# 60_keyboard.net
KiCad netlist of a schematic drawn in EAGLE
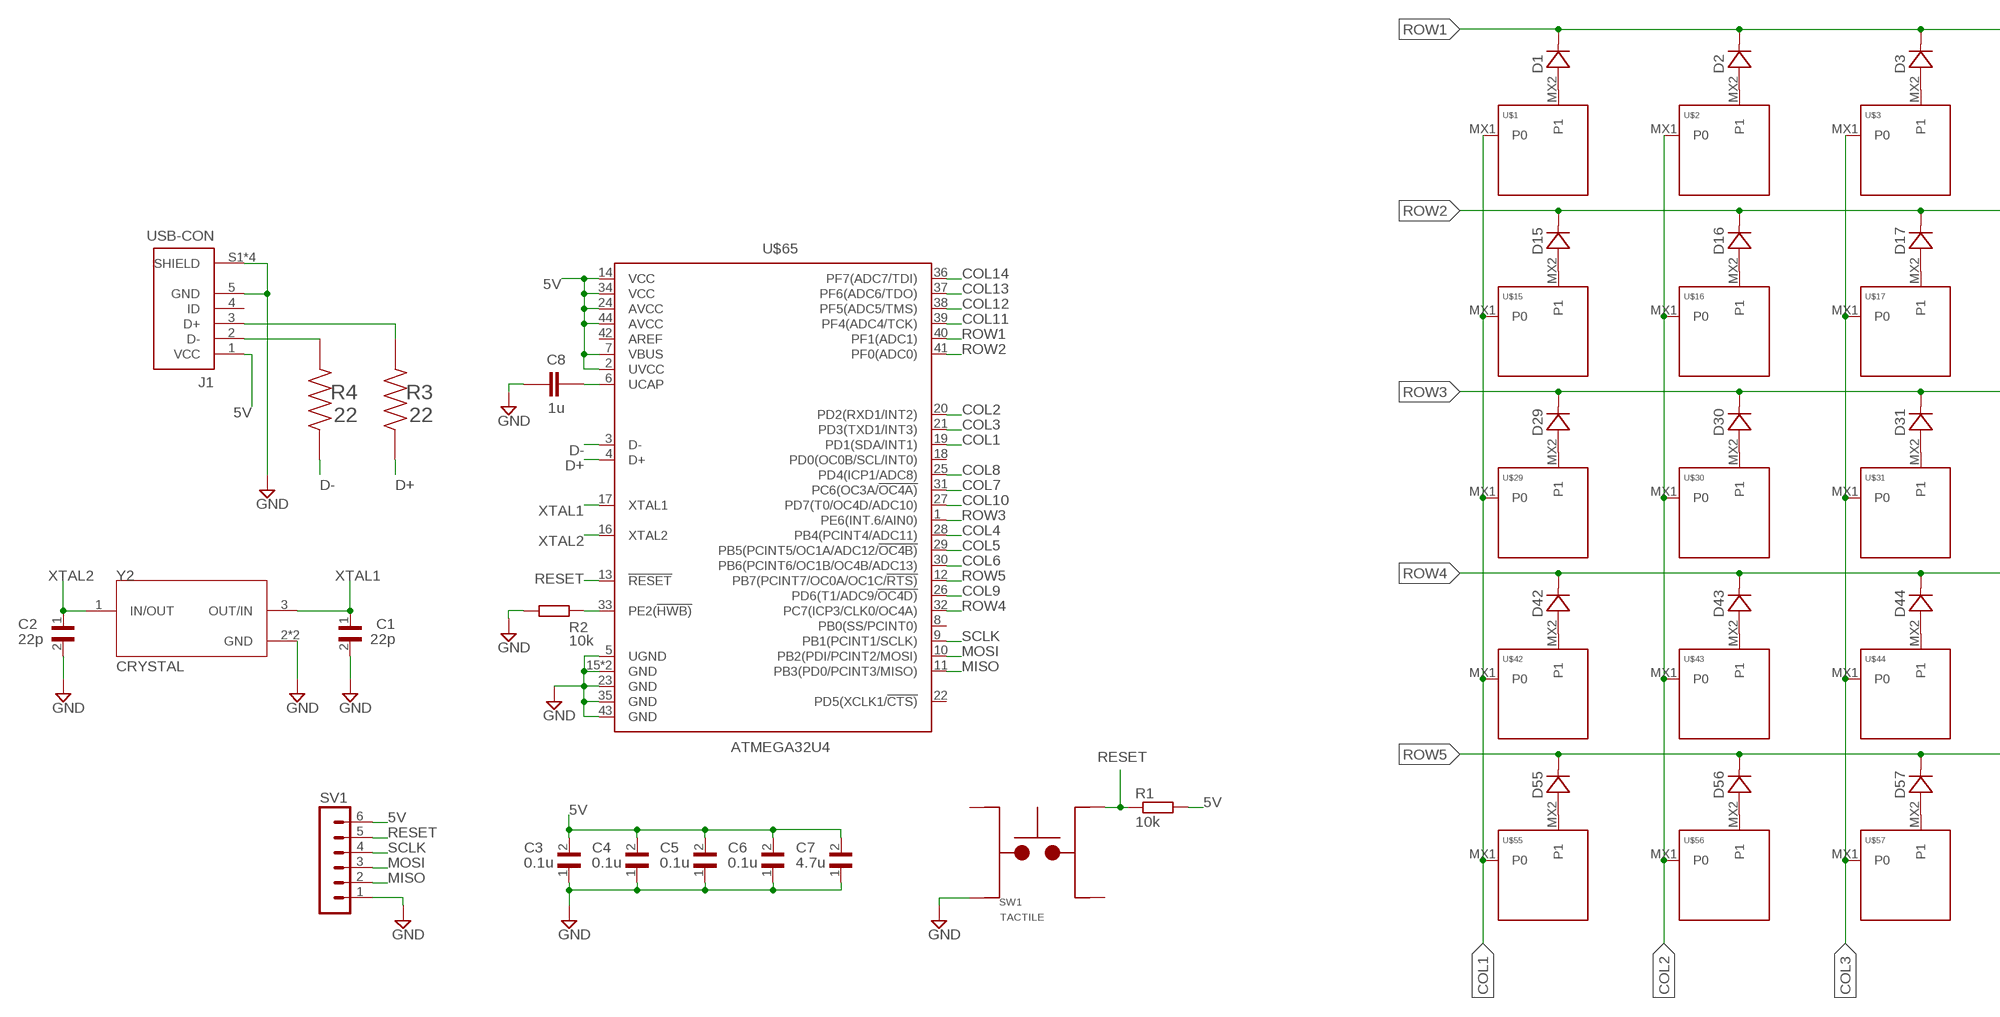
[diagram p0: schematic, sheet 1, part 1 of 2]
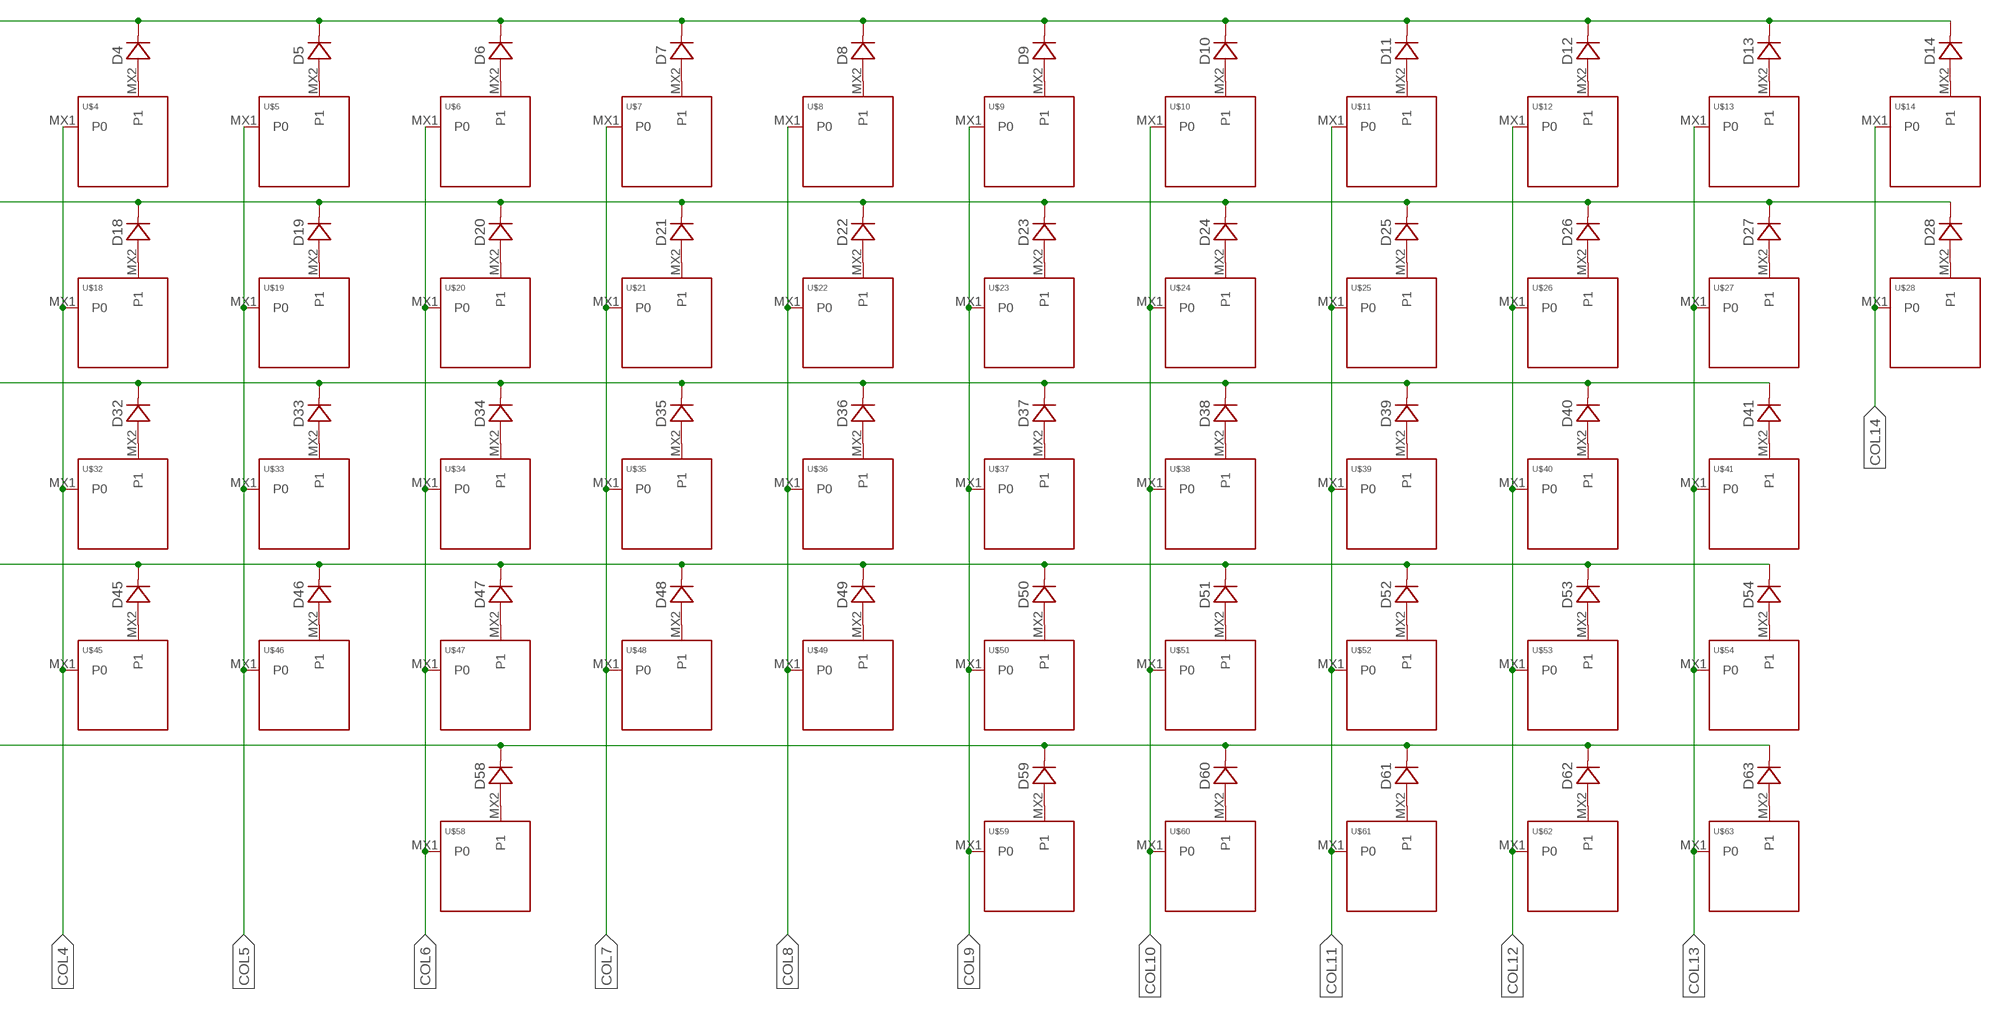
[diagram p1: schematic, sheet 1, part 2 of 2]

(export (version "E")
  (design (tool "Eeschema 10.0.6"))
  (components
    (comp (ref "C1")
      (value "22p")
      (footprint "eagle-import:CAPC2012X140N")
      (fields
        (field (name "DIGI-KEY_PART_NUMBER") "399-C0805C220J5GAC7800CT-ND")
        (field (name "MF") "KEMET")
        (field (name "MP") "C0805C220J5GACTU")
      )
      (libsource (lib "eagle-import") (part "C0805C220J5GACTU"))
    )
    (comp (ref "C2")
      (value "22p")
      (footprint "eagle-import:CAPC2012X140N")
      (fields
        (field (name "DIGI-KEY_PART_NUMBER") "399-C0805C220J5GAC7800CT-ND")
        (field (name "MF") "KEMET")
        (field (name "MP") "C0805C220J5GACTU")
      )
      (libsource (lib "eagle-import") (part "C0805C220J5GACTU"))
    )
    (comp (ref "C3")
      (value "0.1u")
      (footprint "eagle-import:CAPC2012X140N")
      (fields
        (field (name "DIGI-KEY_PART_NUMBER") "478-3614-2-ND")
        (field (name "MF") "AVX")
        (field (name "MP") "08055F104K4T2A")
      )
      (libsource (lib "eagle-import") (part "08055F104K4T2A"))
    )
    (comp (ref "C4")
      (value "0.1u")
      (footprint "eagle-import:CAPC2012X140N")
      (fields
        (field (name "DIGI-KEY_PART_NUMBER") "478-3614-2-ND")
        (field (name "MF") "AVX")
        (field (name "MP") "08055F104K4T2A")
      )
      (libsource (lib "eagle-import") (part "08055F104K4T2A"))
    )
    (comp (ref "C5")
      (value "0.1u")
      (footprint "eagle-import:CAPC2012X140N")
      (fields
        (field (name "DIGI-KEY_PART_NUMBER") "478-3614-2-ND")
        (field (name "MF") "AVX")
        (field (name "MP") "08055F104K4T2A")
      )
      (libsource (lib "eagle-import") (part "08055F104K4T2A"))
    )
    (comp (ref "C6")
      (value "0.1u")
      (footprint "eagle-import:CAPC2012X140N")
      (fields
        (field (name "DIGI-KEY_PART_NUMBER") "478-3614-2-ND")
        (field (name "MF") "AVX")
        (field (name "MP") "08055F104K4T2A")
      )
      (libsource (lib "eagle-import") (part "08055F104K4T2A"))
    )
    (comp (ref "C7")
      (value "4.7u")
      (footprint "eagle-import:CAPC2012X140N")
      (fields
        (field (name "DIGI-KEY_PART_NUMBER") "1276-1244-1-ND")
        (field (name "MF") "Samsung Electro-Mechanics")
        (field (name "MP") "CL21A475KAQNNNE")
      )
      (libsource (lib "eagle-import") (part "CL21A475KAQNNNE"))
    )
    (comp (ref "C8")
      (value "1u")
      (footprint "eagle-import:C0805")
      (libsource (lib "eagle-import") (part "CAPACITOR-C0805"))
    )
    (comp (ref "D1")
      (value "DIODE-SOD-123")
      (footprint "eagle-import:SOD-123")
      (libsource (lib "eagle-import") (part "DIODE-SOD-123"))
    )
    (comp (ref "D2")
      (value "DIODE-SOD-123")
      (footprint "eagle-import:SOD-123")
      (libsource (lib "eagle-import") (part "DIODE-SOD-123"))
    )
    (comp (ref "D3")
      (value "DIODE-SOD-123")
      (footprint "eagle-import:SOD-123")
      (libsource (lib "eagle-import") (part "DIODE-SOD-123"))
    )
    (comp (ref "D4")
      (value "DIODE-SOD-123")
      (footprint "eagle-import:SOD-123")
      (libsource (lib "eagle-import") (part "DIODE-SOD-123"))
    )
    (comp (ref "D5")
      (value "DIODE-SOD-123")
      (footprint "eagle-import:SOD-123")
      (libsource (lib "eagle-import") (part "DIODE-SOD-123"))
    )
    (comp (ref "D6")
      (value "DIODE-SOD-123")
      (footprint "eagle-import:SOD-123")
      (libsource (lib "eagle-import") (part "DIODE-SOD-123"))
    )
    (comp (ref "D7")
      (value "DIODE-SOD-123")
      (footprint "eagle-import:SOD-123")
      (libsource (lib "eagle-import") (part "DIODE-SOD-123"))
    )
    (comp (ref "D8")
      (value "DIODE-SOD-123")
      (footprint "eagle-import:SOD-123")
      (libsource (lib "eagle-import") (part "DIODE-SOD-123"))
    )
    (comp (ref "D9")
      (value "DIODE-SOD-123")
      (footprint "eagle-import:SOD-123")
      (libsource (lib "eagle-import") (part "DIODE-SOD-123"))
    )
    (comp (ref "D10")
      (value "DIODE-SOD-123")
      (footprint "eagle-import:SOD-123")
      (libsource (lib "eagle-import") (part "DIODE-SOD-123"))
    )
    (comp (ref "D11")
      (value "DIODE-SOD-123")
      (footprint "eagle-import:SOD-123")
      (libsource (lib "eagle-import") (part "DIODE-SOD-123"))
    )
    (comp (ref "D12")
      (value "DIODE-SOD-123")
      (footprint "eagle-import:SOD-123")
      (libsource (lib "eagle-import") (part "DIODE-SOD-123"))
    )
    (comp (ref "D13")
      (value "DIODE-SOD-123")
      (footprint "eagle-import:SOD-123")
      (libsource (lib "eagle-import") (part "DIODE-SOD-123"))
    )
    (comp (ref "D14")
      (value "DIODE-SOD-123")
      (footprint "eagle-import:SOD-123")
      (libsource (lib "eagle-import") (part "DIODE-SOD-123"))
    )
    (comp (ref "D15")
      (value "DIODE-SOD-123")
      (footprint "eagle-import:SOD-123")
      (libsource (lib "eagle-import") (part "DIODE-SOD-123"))
    )
    (comp (ref "D16")
      (value "DIODE-SOD-123")
      (footprint "eagle-import:SOD-123")
      (libsource (lib "eagle-import") (part "DIODE-SOD-123"))
    )
    (comp (ref "D17")
      (value "DIODE-SOD-123")
      (footprint "eagle-import:SOD-123")
      (libsource (lib "eagle-import") (part "DIODE-SOD-123"))
    )
    (comp (ref "D18")
      (value "DIODE-SOD-123")
      (footprint "eagle-import:SOD-123")
      (libsource (lib "eagle-import") (part "DIODE-SOD-123"))
    )
    (comp (ref "D19")
      (value "DIODE-SOD-123")
      (footprint "eagle-import:SOD-123")
      (libsource (lib "eagle-import") (part "DIODE-SOD-123"))
    )
    (comp (ref "D20")
      (value "DIODE-SOD-123")
      (footprint "eagle-import:SOD-123")
      (libsource (lib "eagle-import") (part "DIODE-SOD-123"))
    )
    (comp (ref "D21")
      (value "DIODE-SOD-123")
      (footprint "eagle-import:SOD-123")
      (libsource (lib "eagle-import") (part "DIODE-SOD-123"))
    )
    (comp (ref "D22")
      (value "DIODE-SOD-123")
      (footprint "eagle-import:SOD-123")
      (libsource (lib "eagle-import") (part "DIODE-SOD-123"))
    )
    (comp (ref "D23")
      (value "DIODE-SOD-123")
      (footprint "eagle-import:SOD-123")
      (libsource (lib "eagle-import") (part "DIODE-SOD-123"))
    )
    (comp (ref "D24")
      (value "DIODE-SOD-123")
      (footprint "eagle-import:SOD-123")
      (libsource (lib "eagle-import") (part "DIODE-SOD-123"))
    )
    (comp (ref "D25")
      (value "DIODE-SOD-123")
      (footprint "eagle-import:SOD-123")
      (libsource (lib "eagle-import") (part "DIODE-SOD-123"))
    )
    (comp (ref "D26")
      (value "DIODE-SOD-123")
      (footprint "eagle-import:SOD-123")
      (libsource (lib "eagle-import") (part "DIODE-SOD-123"))
    )
    (comp (ref "D27")
      (value "DIODE-SOD-123")
      (footprint "eagle-import:SOD-123")
      (libsource (lib "eagle-import") (part "DIODE-SOD-123"))
    )
    (comp (ref "D28")
      (value "DIODE-SOD-123")
      (footprint "eagle-import:SOD-123")
      (libsource (lib "eagle-import") (part "DIODE-SOD-123"))
    )
    (comp (ref "D29")
      (value "DIODE-SOD-123")
      (footprint "eagle-import:SOD-123")
      (libsource (lib "eagle-import") (part "DIODE-SOD-123"))
    )
    (comp (ref "D30")
      (value "DIODE-SOD-123")
      (footprint "eagle-import:SOD-123")
      (libsource (lib "eagle-import") (part "DIODE-SOD-123"))
    )
    (comp (ref "D31")
      (value "DIODE-SOD-123")
      (footprint "eagle-import:SOD-123")
      (libsource (lib "eagle-import") (part "DIODE-SOD-123"))
    )
    (comp (ref "D32")
      (value "DIODE-SOD-123")
      (footprint "eagle-import:SOD-123")
      (libsource (lib "eagle-import") (part "DIODE-SOD-123"))
    )
    (comp (ref "D33")
      (value "DIODE-SOD-123")
      (footprint "eagle-import:SOD-123")
      (libsource (lib "eagle-import") (part "DIODE-SOD-123"))
    )
    (comp (ref "D34")
      (value "DIODE-SOD-123")
      (footprint "eagle-import:SOD-123")
      (libsource (lib "eagle-import") (part "DIODE-SOD-123"))
    )
    (comp (ref "D35")
      (value "DIODE-SOD-123")
      (footprint "eagle-import:SOD-123")
      (libsource (lib "eagle-import") (part "DIODE-SOD-123"))
    )
    (comp (ref "D36")
      (value "DIODE-SOD-123")
      (footprint "eagle-import:SOD-123")
      (libsource (lib "eagle-import") (part "DIODE-SOD-123"))
    )
    (comp (ref "D37")
      (value "DIODE-SOD-123")
      (footprint "eagle-import:SOD-123")
      (libsource (lib "eagle-import") (part "DIODE-SOD-123"))
    )
    (comp (ref "D38")
      (value "DIODE-SOD-123")
      (footprint "eagle-import:SOD-123")
      (libsource (lib "eagle-import") (part "DIODE-SOD-123"))
    )
    (comp (ref "D39")
      (value "DIODE-SOD-123")
      (footprint "eagle-import:SOD-123")
      (libsource (lib "eagle-import") (part "DIODE-SOD-123"))
    )
    (comp (ref "D40")
      (value "DIODE-SOD-123")
      (footprint "eagle-import:SOD-123")
      (libsource (lib "eagle-import") (part "DIODE-SOD-123"))
    )
    (comp (ref "D41")
      (value "DIODE-SOD-123")
      (footprint "eagle-import:SOD-123")
      (libsource (lib "eagle-import") (part "DIODE-SOD-123"))
    )
    (comp (ref "D42")
      (value "DIODE-SOD-123")
      (footprint "eagle-import:SOD-123")
      (libsource (lib "eagle-import") (part "DIODE-SOD-123"))
    )
    (comp (ref "D43")
      (value "DIODE-SOD-123")
      (footprint "eagle-import:SOD-123")
      (libsource (lib "eagle-import") (part "DIODE-SOD-123"))
    )
    (comp (ref "D44")
      (value "DIODE-SOD-123")
      (footprint "eagle-import:SOD-123")
      (libsource (lib "eagle-import") (part "DIODE-SOD-123"))
    )
    (comp (ref "D45")
      (value "DIODE-SOD-123")
      (footprint "eagle-import:SOD-123")
      (libsource (lib "eagle-import") (part "DIODE-SOD-123"))
    )
    (comp (ref "D46")
      (value "DIODE-SOD-123")
      (footprint "eagle-import:SOD-123")
      (libsource (lib "eagle-import") (part "DIODE-SOD-123"))
    )
    (comp (ref "D47")
      (value "DIODE-SOD-123")
      (footprint "eagle-import:SOD-123")
      (libsource (lib "eagle-import") (part "DIODE-SOD-123"))
    )
    (comp (ref "D48")
      (value "DIODE-SOD-123")
      (footprint "eagle-import:SOD-123")
      (libsource (lib "eagle-import") (part "DIODE-SOD-123"))
    )
    (comp (ref "D49")
      (value "DIODE-SOD-123")
      (footprint "eagle-import:SOD-123")
      (libsource (lib "eagle-import") (part "DIODE-SOD-123"))
    )
    (comp (ref "D50")
      (value "DIODE-SOD-123")
      (footprint "eagle-import:SOD-123")
      (libsource (lib "eagle-import") (part "DIODE-SOD-123"))
    )
    (comp (ref "D51")
      (value "DIODE-SOD-123")
      (footprint "eagle-import:SOD-123")
      (libsource (lib "eagle-import") (part "DIODE-SOD-123"))
    )
    (comp (ref "D52")
      (value "DIODE-SOD-123")
      (footprint "eagle-import:SOD-123")
      (libsource (lib "eagle-import") (part "DIODE-SOD-123"))
    )
    (comp (ref "D53")
      (value "DIODE-SOD-123")
      (footprint "eagle-import:SOD-123")
      (libsource (lib "eagle-import") (part "DIODE-SOD-123"))
    )
    (comp (ref "D54")
      (value "DIODE-SOD-123")
      (footprint "eagle-import:SOD-123")
      (libsource (lib "eagle-import") (part "DIODE-SOD-123"))
    )
    (comp (ref "D55")
      (value "DIODE-SOD-123")
      (footprint "eagle-import:SOD-123")
      (libsource (lib "eagle-import") (part "DIODE-SOD-123"))
    )
    (comp (ref "D56")
      (value "DIODE-SOD-123")
      (footprint "eagle-import:SOD-123")
      (libsource (lib "eagle-import") (part "DIODE-SOD-123"))
    )
    (comp (ref "D57")
      (value "DIODE-SOD-123")
      (footprint "eagle-import:SOD-123")
      (libsource (lib "eagle-import") (part "DIODE-SOD-123"))
    )
    (comp (ref "D58")
      (value "DIODE-SOD-123")
      (footprint "eagle-import:SOD-123")
      (libsource (lib "eagle-import") (part "DIODE-SOD-123"))
    )
    (comp (ref "D59")
      (value "DIODE-SOD-123")
      (footprint "eagle-import:SOD-123")
      (libsource (lib "eagle-import") (part "DIODE-SOD-123"))
    )
    (comp (ref "D60")
      (value "DIODE-SOD-123")
      (footprint "eagle-import:SOD-123")
      (libsource (lib "eagle-import") (part "DIODE-SOD-123"))
    )
    (comp (ref "D61")
      (value "DIODE-SOD-123")
      (footprint "eagle-import:SOD-123")
      (libsource (lib "eagle-import") (part "DIODE-SOD-123"))
    )
    (comp (ref "D62")
      (value "DIODE-SOD-123")
      (footprint "eagle-import:SOD-123")
      (libsource (lib "eagle-import") (part "DIODE-SOD-123"))
    )
    (comp (ref "D63")
      (value "DIODE-SOD-123")
      (footprint "eagle-import:SOD-123")
      (libsource (lib "eagle-import") (part "DIODE-SOD-123"))
    )
    (comp (ref "J1")
      (value "USB-CON")
      (footprint "eagle-import:EDAC_690-005-299-043")
      (fields
        (field (name "DIGI-KEY_PART_NUMBER") "151-1206-2-ND")
        (field (name "MF") "EDAC Inc.")
        (field (name "MP") "690-005-299-043")
      )
      (libsource (lib "eagle-import") (part "690-005-299-043"))
    )
    (comp (ref "R1")
      (value "10k")
      (footprint "eagle-import:R0805")
      (libsource (lib "eagle-import") (part "RESISTOR-0805"))
    )
    (comp (ref "R2")
      (value "10k")
      (footprint "eagle-import:R0805")
      (libsource (lib "eagle-import") (part "RESISTOR-0805"))
    )
    (comp (ref "R3")
      (value "22")
      (footprint "eagle-import:RESC2012X65N")
      (fields
        (field (name "DIGI-KEY_PART_NUMBER") "RMCF0805JT22R0TR-ND")
        (field (name "MF") "Stackpole Electronics Inc")
        (field (name "MP") "RMCF0805JT22R0")
      )
      (libsource (lib "eagle-import") (part "RMCF0805JT22R0"))
    )
    (comp (ref "R4")
      (value "22")
      (footprint "eagle-import:RESC2012X65N")
      (fields
        (field (name "DIGI-KEY_PART_NUMBER") "RMCF0805JT22R0TR-ND")
        (field (name "MF") "Stackpole Electronics Inc")
        (field (name "MP") "RMCF0805JT22R0")
      )
      (libsource (lib "eagle-import") (part "RMCF0805JT22R0"))
    )
    (comp (ref "SV1")
      (value "MA06-1")
      (footprint "eagle-import:MA06-1")
      (libsource (lib "eagle-import") (part "MA06-1"))
    )
    (comp (ref "SW1")
      (value "TACTILE")
      (footprint "eagle-import:SW_TL3342F160QG_TR")
      (fields
        (field (name "DIGI-KEY_PART_NUMBER") "EG2531CT-ND")
        (field (name "MF") "E-Switch")
        (field (name "MP") "TL3342F160QG/TR")
      )
      (libsource (lib "eagle-import") (part "TL3342F160QG/TR"))
    )
    (comp (ref "U$1")
      (value "KEYSWITCH-PLAIN-MXHSPCB-1U")
      (footprint "eagle-import:MXHSPCB-1U")
      (libsource (lib "eagle-import") (part "KEYSWITCH-PLAIN-MXHSPCB-1U"))
    )
    (comp (ref "U$2")
      (value "KEYSWITCH-PLAIN-MXHSPCB-1U")
      (footprint "eagle-import:MXHSPCB-1U")
      (libsource (lib "eagle-import") (part "KEYSWITCH-PLAIN-MXHSPCB-1U"))
    )
    (comp (ref "U$3")
      (value "KEYSWITCH-PLAIN-MXHSPCB-1U")
      (footprint "eagle-import:MXHSPCB-1U")
      (libsource (lib "eagle-import") (part "KEYSWITCH-PLAIN-MXHSPCB-1U"))
    )
    (comp (ref "U$4")
      (value "KEYSWITCH-PLAIN-MXHSPCB-1U")
      (footprint "eagle-import:MXHSPCB-1U")
      (libsource (lib "eagle-import") (part "KEYSWITCH-PLAIN-MXHSPCB-1U"))
    )
    (comp (ref "U$5")
      (value "KEYSWITCH-PLAIN-MXHSPCB-1U")
      (footprint "eagle-import:MXHSPCB-1U")
      (libsource (lib "eagle-import") (part "KEYSWITCH-PLAIN-MXHSPCB-1U"))
    )
    (comp (ref "U$6")
      (value "KEYSWITCH-PLAIN-MXHSPCB-1U")
      (footprint "eagle-import:MXHSPCB-1U")
      (libsource (lib "eagle-import") (part "KEYSWITCH-PLAIN-MXHSPCB-1U"))
    )
    (comp (ref "U$7")
      (value "KEYSWITCH-PLAIN-MXHSPCB-1U")
      (footprint "eagle-import:MXHSPCB-1U")
      (libsource (lib "eagle-import") (part "KEYSWITCH-PLAIN-MXHSPCB-1U"))
    )
    (comp (ref "U$8")
      (value "KEYSWITCH-PLAIN-MXHSPCB-1U")
      (footprint "eagle-import:MXHSPCB-1U")
      (libsource (lib "eagle-import") (part "KEYSWITCH-PLAIN-MXHSPCB-1U"))
    )
    (comp (ref "U$9")
      (value "KEYSWITCH-PLAIN-MXHSPCB-1U")
      (footprint "eagle-import:MXHSPCB-1U")
      (libsource (lib "eagle-import") (part "KEYSWITCH-PLAIN-MXHSPCB-1U"))
    )
    (comp (ref "U$10")
      (value "KEYSWITCH-PLAIN-MXHSPCB-1U")
      (footprint "eagle-import:MXHSPCB-1U")
      (libsource (lib "eagle-import") (part "KEYSWITCH-PLAIN-MXHSPCB-1U"))
    )
    (comp (ref "U$11")
      (value "KEYSWITCH-PLAIN-MXHSPCB-1U")
      (footprint "eagle-import:MXHSPCB-1U")
      (libsource (lib "eagle-import") (part "KEYSWITCH-PLAIN-MXHSPCB-1U"))
    )
    (comp (ref "U$12")
      (value "KEYSWITCH-PLAIN-MXHSPCB-1U")
      (footprint "eagle-import:MXHSPCB-1U")
      (libsource (lib "eagle-import") (part "KEYSWITCH-PLAIN-MXHSPCB-1U"))
    )
    (comp (ref "U$13")
      (value "KEYSWITCH-PLAIN-MXHSPCB-1U")
      (footprint "eagle-import:MXHSPCB-1U")
      (libsource (lib "eagle-import") (part "KEYSWITCH-PLAIN-MXHSPCB-1U"))
    )
    (comp (ref "U$14")
      (value "KEYSWITCH-PLAIN-MXHSPCB-2U")
      (footprint "eagle-import:MXHSPCB-2U")
      (libsource (lib "eagle-import") (part "KEYSWITCH-PLAIN-MXHSPCB-2U"))
    )
    (comp (ref "U$15")
      (value "KEYSWITCH-PLAIN-MXHSPCB-1U")
      (footprint "eagle-import:MXHSPCB-1U")
      (libsource (lib "eagle-import") (part "KEYSWITCH-PLAIN-MXHSPCB-1U"))
    )
    (comp (ref "U$16")
      (value "KEYSWITCH-PLAIN-MXHSPCB-1U")
      (footprint "eagle-import:MXHSPCB-1U")
      (libsource (lib "eagle-import") (part "KEYSWITCH-PLAIN-MXHSPCB-1U"))
    )
    (comp (ref "U$17")
      (value "KEYSWITCH-PLAIN-MXHSPCB-1U")
      (footprint "eagle-import:MXHSPCB-1U")
      (libsource (lib "eagle-import") (part "KEYSWITCH-PLAIN-MXHSPCB-1U"))
    )
    (comp (ref "U$18")
      (value "KEYSWITCH-PLAIN-MXHSPCB-1U")
      (footprint "eagle-import:MXHSPCB-1U")
      (libsource (lib "eagle-import") (part "KEYSWITCH-PLAIN-MXHSPCB-1U"))
    )
    (comp (ref "U$19")
      (value "KEYSWITCH-PLAIN-MXHSPCB-1U")
      (footprint "eagle-import:MXHSPCB-1U")
      (libsource (lib "eagle-import") (part "KEYSWITCH-PLAIN-MXHSPCB-1U"))
    )
    (comp (ref "U$20")
      (value "KEYSWITCH-PLAIN-MXHSPCB-1U")
      (footprint "eagle-import:MXHSPCB-1U")
      (libsource (lib "eagle-import") (part "KEYSWITCH-PLAIN-MXHSPCB-1U"))
    )
    (comp (ref "U$21")
      (value "KEYSWITCH-PLAIN-MXHSPCB-1U")
      (footprint "eagle-import:MXHSPCB-1U")
      (libsource (lib "eagle-import") (part "KEYSWITCH-PLAIN-MXHSPCB-1U"))
    )
    (comp (ref "U$22")
      (value "KEYSWITCH-PLAIN-MXHSPCB-1U")
      (footprint "eagle-import:MXHSPCB-1U")
      (libsource (lib "eagle-import") (part "KEYSWITCH-PLAIN-MXHSPCB-1U"))
    )
    (comp (ref "U$23")
      (value "KEYSWITCH-PLAIN-MXHSPCB-1U")
      (footprint "eagle-import:MXHSPCB-1U")
      (libsource (lib "eagle-import") (part "KEYSWITCH-PLAIN-MXHSPCB-1U"))
    )
    (comp (ref "U$24")
      (value "KEYSWITCH-PLAIN-MXHSPCB-1U")
      (footprint "eagle-import:MXHSPCB-1U")
      (libsource (lib "eagle-import") (part "KEYSWITCH-PLAIN-MXHSPCB-1U"))
    )
    (comp (ref "U$25")
      (value "KEYSWITCH-PLAIN-MXHSPCB-1U")
      (footprint "eagle-import:MXHSPCB-1U")
      (libsource (lib "eagle-import") (part "KEYSWITCH-PLAIN-MXHSPCB-1U"))
    )
    (comp (ref "U$26")
      (value "KEYSWITCH-PLAIN-MXHSPCB-1U")
      (footprint "eagle-import:MXHSPCB-1U")
      (libsource (lib "eagle-import") (part "KEYSWITCH-PLAIN-MXHSPCB-1U"))
    )
    (comp (ref "U$27")
      (value "KEYSWITCH-PLAIN-MXHSPCB-1U")
      (footprint "eagle-import:MXHSPCB-1U")
      (libsource (lib "eagle-import") (part "KEYSWITCH-PLAIN-MXHSPCB-1U"))
    )
    (comp (ref "U$28")
      (value "KEYSWITCH-PLAIN-MXHSPCB-1U")
      (footprint "eagle-import:MXHSPCB-1U")
      (libsource (lib "eagle-import") (part "KEYSWITCH-PLAIN-MXHSPCB-1U"))
    )
    (comp (ref "U$29")
      (value "KEYSWITCH-PLAIN-MXHSPCB-1U")
      (footprint "eagle-import:MXHSPCB-1U")
      (libsource (lib "eagle-import") (part "KEYSWITCH-PLAIN-MXHSPCB-1U"))
    )
    (comp (ref "U$30")
      (value "KEYSWITCH-PLAIN-MXHSPCB-1U")
      (footprint "eagle-import:MXHSPCB-1U")
      (libsource (lib "eagle-import") (part "KEYSWITCH-PLAIN-MXHSPCB-1U"))
    )
    (comp (ref "U$31")
      (value "KEYSWITCH-PLAIN-MXHSPCB-1U")
      (footprint "eagle-import:MXHSPCB-1U")
      (libsource (lib "eagle-import") (part "KEYSWITCH-PLAIN-MXHSPCB-1U"))
    )
    (comp (ref "U$32")
      (value "KEYSWITCH-PLAIN-MXHSPCB-1U")
      (footprint "eagle-import:MXHSPCB-1U")
      (libsource (lib "eagle-import") (part "KEYSWITCH-PLAIN-MXHSPCB-1U"))
    )
    (comp (ref "U$33")
      (value "KEYSWITCH-PLAIN-MXHSPCB-1U")
      (footprint "eagle-import:MXHSPCB-1U")
      (libsource (lib "eagle-import") (part "KEYSWITCH-PLAIN-MXHSPCB-1U"))
    )
    (comp (ref "U$34")
      (value "KEYSWITCH-PLAIN-MXHSPCB-1U")
      (footprint "eagle-import:MXHSPCB-1U")
      (libsource (lib "eagle-import") (part "KEYSWITCH-PLAIN-MXHSPCB-1U"))
    )
    (comp (ref "U$35")
      (value "KEYSWITCH-PLAIN-MXHSPCB-1U")
      (footprint "eagle-import:MXHSPCB-1U")
      (libsource (lib "eagle-import") (part "KEYSWITCH-PLAIN-MXHSPCB-1U"))
    )
    (comp (ref "U$36")
      (value "KEYSWITCH-PLAIN-MXHSPCB-1U")
      (footprint "eagle-import:MXHSPCB-1U")
      (libsource (lib "eagle-import") (part "KEYSWITCH-PLAIN-MXHSPCB-1U"))
    )
    (comp (ref "U$37")
      (value "KEYSWITCH-PLAIN-MXHSPCB-1U")
      (footprint "eagle-import:MXHSPCB-1U")
      (libsource (lib "eagle-import") (part "KEYSWITCH-PLAIN-MXHSPCB-1U"))
    )
    (comp (ref "U$38")
      (value "KEYSWITCH-PLAIN-MXHSPCB-1U")
      (footprint "eagle-import:MXHSPCB-1U")
      (libsource (lib "eagle-import") (part "KEYSWITCH-PLAIN-MXHSPCB-1U"))
    )
    (comp (ref "U$39")
      (value "KEYSWITCH-PLAIN-MXHSPCB-1U")
      (footprint "eagle-import:MXHSPCB-1U")
      (libsource (lib "eagle-import") (part "KEYSWITCH-PLAIN-MXHSPCB-1U"))
    )
    (comp (ref "U$40")
      (value "KEYSWITCH-PLAIN-MXHSPCB-1U")
      (footprint "eagle-import:MXHSPCB-1U")
      (libsource (lib "eagle-import") (part "KEYSWITCH-PLAIN-MXHSPCB-1U"))
    )
    (comp (ref "U$41")
      (value "KEYSWITCH-PLAIN-MXHSPCB-2U")
      (footprint "eagle-import:MXHSPCB-2U")
      (libsource (lib "eagle-import") (part "KEYSWITCH-PLAIN-MXHSPCB-2U"))
    )
    (comp (ref "U$42")
      (value "KEYSWITCH-PLAIN-MXHSPCB-2U")
      (footprint "eagle-import:MXHSPCB-2U")
      (libsource (lib "eagle-import") (part "KEYSWITCH-PLAIN-MXHSPCB-2U"))
    )
    (comp (ref "U$43")
      (value "KEYSWITCH-PLAIN-MXHSPCB-1U")
      (footprint "eagle-import:MXHSPCB-1U")
      (libsource (lib "eagle-import") (part "KEYSWITCH-PLAIN-MXHSPCB-1U"))
    )
    (comp (ref "U$44")
      (value "KEYSWITCH-PLAIN-MXHSPCB-1U")
      (footprint "eagle-import:MXHSPCB-1U")
      (libsource (lib "eagle-import") (part "KEYSWITCH-PLAIN-MXHSPCB-1U"))
    )
    (comp (ref "U$45")
      (value "KEYSWITCH-PLAIN-MXHSPCB-1U")
      (footprint "eagle-import:MXHSPCB-1U")
      (libsource (lib "eagle-import") (part "KEYSWITCH-PLAIN-MXHSPCB-1U"))
    )
    (comp (ref "U$46")
      (value "KEYSWITCH-PLAIN-MXHSPCB-1U")
      (footprint "eagle-import:MXHSPCB-1U")
      (libsource (lib "eagle-import") (part "KEYSWITCH-PLAIN-MXHSPCB-1U"))
    )
    (comp (ref "U$47")
      (value "KEYSWITCH-PLAIN-MXHSPCB-1U")
      (footprint "eagle-import:MXHSPCB-1U")
      (libsource (lib "eagle-import") (part "KEYSWITCH-PLAIN-MXHSPCB-1U"))
    )
    (comp (ref "U$48")
      (value "KEYSWITCH-PLAIN-MXHSPCB-1U")
      (footprint "eagle-import:MXHSPCB-1U")
      (libsource (lib "eagle-import") (part "KEYSWITCH-PLAIN-MXHSPCB-1U"))
    )
    (comp (ref "U$49")
      (value "KEYSWITCH-PLAIN-MXHSPCB-1U")
      (footprint "eagle-import:MXHSPCB-1U")
      (libsource (lib "eagle-import") (part "KEYSWITCH-PLAIN-MXHSPCB-1U"))
    )
    (comp (ref "U$50")
      (value "KEYSWITCH-PLAIN-MXHSPCB-1U")
      (footprint "eagle-import:MXHSPCB-1U")
      (libsource (lib "eagle-import") (part "KEYSWITCH-PLAIN-MXHSPCB-1U"))
    )
    (comp (ref "U$51")
      (value "KEYSWITCH-PLAIN-MXHSPCB-1U")
      (footprint "eagle-import:MXHSPCB-1U")
      (libsource (lib "eagle-import") (part "KEYSWITCH-PLAIN-MXHSPCB-1U"))
    )
    (comp (ref "U$52")
      (value "KEYSWITCH-PLAIN-MXHSPCB-1U")
      (footprint "eagle-import:MXHSPCB-1U")
      (libsource (lib "eagle-import") (part "KEYSWITCH-PLAIN-MXHSPCB-1U"))
    )
    (comp (ref "U$53")
      (value "KEYSWITCH-PLAIN-MXHSPCB-1U")
      (footprint "eagle-import:MXHSPCB-1U")
      (libsource (lib "eagle-import") (part "KEYSWITCH-PLAIN-MXHSPCB-1U"))
    )
    (comp (ref "U$54")
      (value "KEYSWITCH-PLAIN-MXHSPCB-1U")
      (footprint "eagle-import:MXHSPCB-1U")
      (libsource (lib "eagle-import") (part "KEYSWITCH-PLAIN-MXHSPCB-1U"))
    )
    (comp (ref "U$55")
      (value "KEYSWITCH-PLAIN-MXHSPCB-1U")
      (footprint "eagle-import:MXHSPCB-1U")
      (libsource (lib "eagle-import") (part "KEYSWITCH-PLAIN-MXHSPCB-1U"))
    )
    (comp (ref "U$56")
      (value "KEYSWITCH-PLAIN-MXHSPCB-1U")
      (footprint "eagle-import:MXHSPCB-1U")
      (libsource (lib "eagle-import") (part "KEYSWITCH-PLAIN-MXHSPCB-1U"))
    )
    (comp (ref "U$57")
      (value "KEYSWITCH-PLAIN-MXHSPCB-1U")
      (footprint "eagle-import:MXHSPCB-1U")
      (libsource (lib "eagle-import") (part "KEYSWITCH-PLAIN-MXHSPCB-1U"))
    )
    (comp (ref "U$58")
      (value "KEYSWITCH-PLAIN-MXHSPCB-6.25U-FLIPPED")
      (footprint "eagle-import:MXHSPCB-6.25U-FLIPPED")
      (libsource (lib "eagle-import") (part "KEYSWITCH-PLAIN-MXHSPCB-6.25U-FLIPPED"))
    )
    (comp (ref "U$59")
      (value "KEYSWITCH-PLAIN-MXHSPCB-1U")
      (footprint "eagle-import:MXHSPCB-1U")
      (libsource (lib "eagle-import") (part "KEYSWITCH-PLAIN-MXHSPCB-1U"))
    )
    (comp (ref "U$60")
      (value "KEYSWITCH-PLAIN-MXHSPCB-1U")
      (footprint "eagle-import:MXHSPCB-1U")
      (libsource (lib "eagle-import") (part "KEYSWITCH-PLAIN-MXHSPCB-1U"))
    )
    (comp (ref "U$61")
      (value "KEYSWITCH-PLAIN-MXHSPCB-1U")
      (footprint "eagle-import:MXHSPCB-1U")
      (libsource (lib "eagle-import") (part "KEYSWITCH-PLAIN-MXHSPCB-1U"))
    )
    (comp (ref "U$62")
      (value "KEYSWITCH-PLAIN-MXHSPCB-1U")
      (footprint "eagle-import:MXHSPCB-1U")
      (libsource (lib "eagle-import") (part "KEYSWITCH-PLAIN-MXHSPCB-1U"))
    )
    (comp (ref "U$63")
      (value "KEYSWITCH-PLAIN-MXHSPCB-1U")
      (footprint "eagle-import:MXHSPCB-1U")
      (libsource (lib "eagle-import") (part "KEYSWITCH-PLAIN-MXHSPCB-1U"))
    )
    (comp (ref "U$65")
      (value "ATMEGA32U4")
      (footprint "eagle-import:QFN-44")
      (libsource (lib "eagle-import") (part "ATMEGA32U4-QFN44"))
    )
    (comp (ref "Y2")
      (value "CRYSTAL")
      (footprint "eagle-import:XTAL_ECS-160-12-33-AGN-TR")
      (fields
        (field (name "DIGI-KEY_PART_NUMBER") "XC2930TR-ND")
        (field (name "MF") "ECS Inc.")
        (field (name "MP") "ECS-160-12-33-AGN-TR")
      )
      (libsource (lib "eagle-import") (part "ECS-160-12-33-AGN-TR"))
    )
  )
  (nets
    (net (code "1") (name "/5V") (class "Default")
      (node (ref "C3") (pin "2") (pinfunction "2_2") (pintype "passive"))
      (node (ref "C4") (pin "2") (pinfunction "2_2") (pintype "passive"))
      (node (ref "C5") (pin "2") (pinfunction "2_2") (pintype "passive"))
      (node (ref "C6") (pin "2") (pinfunction "2_2") (pintype "passive"))
      (node (ref "C7") (pin "2") (pinfunction "2_2") (pintype "passive"))
      (node (ref "J1") (pin "1") (pinfunction "VCC_1") (pintype "power_in"))
      (node (ref "R1") (pin "2") (pinfunction "2_2") (pintype "passive"))
      (node (ref "SV1") (pin "6") (pinfunction "6_6") (pintype "passive"))
      (node (ref "U$65") (pin "14") (pinfunction "VCC_14") (pintype "bidirectional"))
      (node (ref "U$65") (pin "2") (pinfunction "UVCC_2") (pintype "bidirectional"))
      (node (ref "U$65") (pin "24") (pinfunction "AVCC_24") (pintype "bidirectional"))
      (node (ref "U$65") (pin "34") (pinfunction "VCC_34") (pintype "bidirectional"))
      (node (ref "U$65") (pin "44") (pinfunction "AVCC_44") (pintype "bidirectional"))
      (node (ref "U$65") (pin "7") (pinfunction "VBUS_7") (pintype "bidirectional"))
    )
    (net (code "2") (name "/D+") (class "Default")
      (node (ref "R3") (pin "1") (pinfunction "1_1") (pintype "passive"))
      (node (ref "U$65") (pin "4") (pinfunction "D+_4") (pintype "bidirectional"))
    )
    (net (code "3") (name "/D-") (class "Default")
      (node (ref "R4") (pin "1") (pinfunction "1_1") (pintype "passive"))
      (node (ref "U$65") (pin "3") (pinfunction "D-_3") (pintype "bidirectional"))
    )
    (net (code "4") (name "/MISO") (class "Default")
      (node (ref "SV1") (pin "2") (pinfunction "2_2") (pintype "passive"))
      (node (ref "U$65") (pin "11") (pinfunction "PB3(PD0/PCINT3/MISO)_11") (pintype "bidirectional"))
    )
    (net (code "5") (name "/MOSI") (class "Default")
      (node (ref "SV1") (pin "3") (pinfunction "3_3") (pintype "passive"))
      (node (ref "U$65") (pin "10") (pinfunction "PB2(PDI/PCINT2/MOSI)_10") (pintype "bidirectional"))
    )
    (net (code "6") (name "/RESET") (class "Default")
      (node (ref "R1") (pin "1") (pinfunction "1_1") (pintype "passive"))
      (node (ref "SV1") (pin "5") (pinfunction "5_5") (pintype "passive"))
      (node (ref "SW1") (pin "2") (pinfunction "2_2") (pintype "passive"))
      (node (ref "U$65") (pin "13") (pinfunction "~{RESET}_13") (pintype "bidirectional"))
    )
    (net (code "7") (name "/SCLK") (class "Default")
      (node (ref "SV1") (pin "4") (pinfunction "4_4") (pintype "passive"))
      (node (ref "U$65") (pin "9") (pinfunction "PB1(PCINT1/SCLK)_9") (pintype "bidirectional"))
    )
    (net (code "8") (name "/XTAL1") (class "Default")
      (node (ref "C1") (pin "1") (pinfunction "1_1") (pintype "passive"))
      (node (ref "U$65") (pin "17") (pinfunction "XTAL1_17") (pintype "bidirectional"))
      (node (ref "Y2") (pin "3") (pinfunction "OUT/IN_3") (pintype "bidirectional"))
    )
    (net (code "9") (name "/XTAL2") (class "Default")
      (node (ref "C2") (pin "1") (pinfunction "1_1") (pintype "passive"))
      (node (ref "U$65") (pin "16") (pinfunction "XTAL2_16") (pintype "bidirectional"))
      (node (ref "Y2") (pin "1") (pinfunction "IN/OUT_1") (pintype "bidirectional"))
    )
    (net (code "10") (name "COL1") (class "Default")
      (node (ref "U$1") (pin "MX1") (pinfunction "P0_MX1") (pintype "bidirectional"))
      (node (ref "U$15") (pin "MX1") (pinfunction "P0_MX1") (pintype "bidirectional"))
      (node (ref "U$29") (pin "MX1") (pinfunction "P0_MX1") (pintype "bidirectional"))
      (node (ref "U$42") (pin "MX1") (pinfunction "P0_MX1") (pintype "bidirectional"))
      (node (ref "U$55") (pin "MX1") (pinfunction "P0_MX1") (pintype "bidirectional"))
      (node (ref "U$65") (pin "19") (pinfunction "PD1(SDA/INT1)_19") (pintype "bidirectional"))
    )
    (net (code "11") (name "COL2") (class "Default")
      (node (ref "U$16") (pin "MX1") (pinfunction "P0_MX1") (pintype "bidirectional"))
      (node (ref "U$2") (pin "MX1") (pinfunction "P0_MX1") (pintype "bidirectional"))
      (node (ref "U$30") (pin "MX1") (pinfunction "P0_MX1") (pintype "bidirectional"))
      (node (ref "U$43") (pin "MX1") (pinfunction "P0_MX1") (pintype "bidirectional"))
      (node (ref "U$56") (pin "MX1") (pinfunction "P0_MX1") (pintype "bidirectional"))
      (node (ref "U$65") (pin "20") (pinfunction "PD2(RXD1/INT2)_20") (pintype "bidirectional"))
    )
    (net (code "12") (name "COL3") (class "Default")
      (node (ref "U$17") (pin "MX1") (pinfunction "P0_MX1") (pintype "bidirectional"))
      (node (ref "U$3") (pin "MX1") (pinfunction "P0_MX1") (pintype "bidirectional"))
      (node (ref "U$31") (pin "MX1") (pinfunction "P0_MX1") (pintype "bidirectional"))
      (node (ref "U$44") (pin "MX1") (pinfunction "P0_MX1") (pintype "bidirectional"))
      (node (ref "U$57") (pin "MX1") (pinfunction "P0_MX1") (pintype "bidirectional"))
      (node (ref "U$65") (pin "21") (pinfunction "PD3(TXD1/INT3)_21") (pintype "bidirectional"))
    )
    (net (code "13") (name "COL4") (class "Default")
      (node (ref "U$18") (pin "MX1") (pinfunction "P0_MX1") (pintype "bidirectional"))
      (node (ref "U$32") (pin "MX1") (pinfunction "P0_MX1") (pintype "bidirectional"))
      (node (ref "U$4") (pin "MX1") (pinfunction "P0_MX1") (pintype "bidirectional"))
      (node (ref "U$45") (pin "MX1") (pinfunction "P0_MX1") (pintype "bidirectional"))
      (node (ref "U$65") (pin "28") (pinfunction "PB4(PCINT4/ADC11)_28") (pintype "bidirectional"))
    )
    (net (code "14") (name "COL5") (class "Default")
      (node (ref "U$19") (pin "MX1") (pinfunction "P0_MX1") (pintype "bidirectional"))
      (node (ref "U$33") (pin "MX1") (pinfunction "P0_MX1") (pintype "bidirectional"))
      (node (ref "U$46") (pin "MX1") (pinfunction "P0_MX1") (pintype "bidirectional"))
      (node (ref "U$5") (pin "MX1") (pinfunction "P0_MX1") (pintype "bidirectional"))
      (node (ref "U$65") (pin "29") (pinfunction "PB5(PCINT5/OC1A/ADC12/~{OC4B})_29") (pintype "bidirectional"))
    )
    (net (code "15") (name "COL6") (class "Default")
      (node (ref "U$20") (pin "MX1") (pinfunction "P0_MX1") (pintype "bidirectional"))
      (node (ref "U$34") (pin "MX1") (pinfunction "P0_MX1") (pintype "bidirectional"))
      (node (ref "U$47") (pin "MX1") (pinfunction "P0_MX1") (pintype "bidirectional"))
      (node (ref "U$58") (pin "MX1") (pinfunction "P0_MX1") (pintype "bidirectional"))
      (node (ref "U$6") (pin "MX1") (pinfunction "P0_MX1") (pintype "bidirectional"))
      (node (ref "U$65") (pin "30") (pinfunction "PB6(PCINT6/OC1B/OC4B/ADC13)_30") (pintype "bidirectional"))
    )
    (net (code "16") (name "COL7") (class "Default")
      (node (ref "U$21") (pin "MX1") (pinfunction "P0_MX1") (pintype "bidirectional"))
      (node (ref "U$35") (pin "MX1") (pinfunction "P0_MX1") (pintype "bidirectional"))
      (node (ref "U$48") (pin "MX1") (pinfunction "P0_MX1") (pintype "bidirectional"))
      (node (ref "U$65") (pin "31") (pinfunction "PC6(OC3A/~{OC4A})_31") (pintype "bidirectional"))
      (node (ref "U$7") (pin "MX1") (pinfunction "P0_MX1") (pintype "bidirectional"))
    )
    (net (code "17") (name "COL8") (class "Default")
      (node (ref "U$22") (pin "MX1") (pinfunction "P0_MX1") (pintype "bidirectional"))
      (node (ref "U$36") (pin "MX1") (pinfunction "P0_MX1") (pintype "bidirectional"))
      (node (ref "U$49") (pin "MX1") (pinfunction "P0_MX1") (pintype "bidirectional"))
      (node (ref "U$65") (pin "25") (pinfunction "PD4(ICP1/ADC8)_25") (pintype "bidirectional"))
      (node (ref "U$8") (pin "MX1") (pinfunction "P0_MX1") (pintype "bidirectional"))
    )
    (net (code "18") (name "COL9") (class "Default")
      (node (ref "U$23") (pin "MX1") (pinfunction "P0_MX1") (pintype "bidirectional"))
      (node (ref "U$37") (pin "MX1") (pinfunction "P0_MX1") (pintype "bidirectional"))
      (node (ref "U$50") (pin "MX1") (pinfunction "P0_MX1") (pintype "bidirectional"))
      (node (ref "U$59") (pin "MX1") (pinfunction "P0_MX1") (pintype "bidirectional"))
      (node (ref "U$65") (pin "26") (pinfunction "PD6(T1/ADC9/~{OC4D})_26") (pintype "bidirectional"))
      (node (ref "U$9") (pin "MX1") (pinfunction "P0_MX1") (pintype "bidirectional"))
    )
    (net (code "19") (name "COL10") (class "Default")
      (node (ref "U$10") (pin "MX1") (pinfunction "P0_MX1") (pintype "bidirectional"))
      (node (ref "U$24") (pin "MX1") (pinfunction "P0_MX1") (pintype "bidirectional"))
      (node (ref "U$38") (pin "MX1") (pinfunction "P0_MX1") (pintype "bidirectional"))
      (node (ref "U$51") (pin "MX1") (pinfunction "P0_MX1") (pintype "bidirectional"))
      (node (ref "U$60") (pin "MX1") (pinfunction "P0_MX1") (pintype "bidirectional"))
      (node (ref "U$65") (pin "27") (pinfunction "PD7(T0/OC4D/ADC10)_27") (pintype "bidirectional"))
    )
    (net (code "20") (name "COL11") (class "Default")
      (node (ref "U$11") (pin "MX1") (pinfunction "P0_MX1") (pintype "bidirectional"))
      (node (ref "U$25") (pin "MX1") (pinfunction "P0_MX1") (pintype "bidirectional"))
      (node (ref "U$39") (pin "MX1") (pinfunction "P0_MX1") (pintype "bidirectional"))
      (node (ref "U$52") (pin "MX1") (pinfunction "P0_MX1") (pintype "bidirectional"))
      (node (ref "U$61") (pin "MX1") (pinfunction "P0_MX1") (pintype "bidirectional"))
      (node (ref "U$65") (pin "39") (pinfunction "PF4(ADC4/TCK)_39") (pintype "bidirectional"))
    )
    (net (code "21") (name "COL12") (class "Default")
      (node (ref "U$12") (pin "MX1") (pinfunction "P0_MX1") (pintype "bidirectional"))
      (node (ref "U$26") (pin "MX1") (pinfunction "P0_MX1") (pintype "bidirectional"))
      (node (ref "U$40") (pin "MX1") (pinfunction "P0_MX1") (pintype "bidirectional"))
      (node (ref "U$53") (pin "MX1") (pinfunction "P0_MX1") (pintype "bidirectional"))
      (node (ref "U$62") (pin "MX1") (pinfunction "P0_MX1") (pintype "bidirectional"))
      (node (ref "U$65") (pin "38") (pinfunction "PF5(ADC5/TMS)_38") (pintype "bidirectional"))
    )
    (net (code "22") (name "COL13") (class "Default")
      (node (ref "U$13") (pin "MX1") (pinfunction "P0_MX1") (pintype "bidirectional"))
      (node (ref "U$27") (pin "MX1") (pinfunction "P0_MX1") (pintype "bidirectional"))
      (node (ref "U$41") (pin "MX1") (pinfunction "P0_MX1") (pintype "bidirectional"))
      (node (ref "U$54") (pin "MX1") (pinfunction "P0_MX1") (pintype "bidirectional"))
      (node (ref "U$63") (pin "MX1") (pinfunction "P0_MX1") (pintype "bidirectional"))
      (node (ref "U$65") (pin "37") (pinfunction "PF6(ADC6/TDO)_37") (pintype "bidirectional"))
    )
    (net (code "23") (name "COL14") (class "Default")
      (node (ref "U$14") (pin "MX1") (pinfunction "P0_MX1") (pintype "bidirectional"))
      (node (ref "U$28") (pin "MX1") (pinfunction "P0_MX1") (pintype "bidirectional"))
      (node (ref "U$65") (pin "36") (pinfunction "PF7(ADC7/TDI)_36") (pintype "bidirectional"))
    )
    (net (code "24") (name "GND") (class "Default")
      (node (ref "C1") (pin "2") (pinfunction "2_2") (pintype "passive"))
      (node (ref "C2") (pin "2") (pinfunction "2_2") (pintype "passive"))
      (node (ref "C3") (pin "1") (pinfunction "1_1") (pintype "passive"))
      (node (ref "C4") (pin "1") (pinfunction "1_1") (pintype "passive"))
      (node (ref "C5") (pin "1") (pinfunction "1_1") (pintype "passive"))
      (node (ref "C6") (pin "1") (pinfunction "1_1") (pintype "passive"))
      (node (ref "C7") (pin "1") (pinfunction "1_1") (pintype "passive"))
      (node (ref "C8") (pin "2") (pinfunction "2_2") (pintype "passive"))
      (node (ref "J1") (pin "5") (pinfunction "GND_5") (pintype "power_in"))
      (node (ref "J1") (pin "S1") (pinfunction "SHIELD_S1") (pintype "passive"))
      (node (ref "J1") (pin "S2") (pinfunction "SHIELD_S2") (pintype "passive"))
      (node (ref "J1") (pin "S3") (pinfunction "SHIELD_S3") (pintype "passive"))
      (node (ref "J1") (pin "S4") (pinfunction "SHIELD_S4") (pintype "passive"))
      (node (ref "R2") (pin "1") (pinfunction "1_1") (pintype "passive"))
      (node (ref "SV1") (pin "1") (pinfunction "1_1") (pintype "passive"))
      (node (ref "SW1") (pin "3") (pinfunction "3_3") (pintype "passive"))
      (node (ref "U$65") (pin "15") (pinfunction "GND_15") (pintype "bidirectional"))
      (node (ref "U$65") (pin "23") (pinfunction "GND_23") (pintype "bidirectional"))
      (node (ref "U$65") (pin "35") (pinfunction "GND_35") (pintype "bidirectional"))
      (node (ref "U$65") (pin "43") (pinfunction "GND_43") (pintype "bidirectional"))
      (node (ref "U$65") (pin "5") (pinfunction "UGND_5") (pintype "bidirectional"))
      (node (ref "U$65") (pin "TAB") (pinfunction "GND_TAB") (pintype "bidirectional"))
      (node (ref "Y2") (pin "2") (pinfunction "GND_2") (pintype "power_in"))
      (node (ref "Y2") (pin "4") (pinfunction "GND_4") (pintype "power_in"))
    )
    (net (code "25") (name "Net-(J1-D+)") (class "Default")
      (node (ref "J1") (pin "3") (pinfunction "D+_3") (pintype "bidirectional"))
      (node (ref "R3") (pin "2") (pinfunction "2_2") (pintype "passive"))
    )
    (net (code "26") (name "Net-(J1-D-)") (class "Default")
      (node (ref "J1") (pin "2") (pinfunction "D-_2") (pintype "bidirectional"))
      (node (ref "R4") (pin "2") (pinfunction "2_2") (pintype "passive"))
    )
    (net (code "27") (name "Net-(U$1-P1)") (class "Default")
      (node (ref "D1") (pin "A") (pinfunction "A_A") (pintype "passive"))
      (node (ref "U$1") (pin "MX2") (pinfunction "P1_MX2") (pintype "bidirectional"))
    )
    (net (code "28") (name "Net-(U$2-P1)") (class "Default")
      (node (ref "D2") (pin "A") (pinfunction "A_A") (pintype "passive"))
      (node (ref "U$2") (pin "MX2") (pinfunction "P1_MX2") (pintype "bidirectional"))
    )
    (net (code "29") (name "Net-(U$3-P1)") (class "Default")
      (node (ref "D3") (pin "A") (pinfunction "A_A") (pintype "passive"))
      (node (ref "U$3") (pin "MX2") (pinfunction "P1_MX2") (pintype "bidirectional"))
    )
    (net (code "30") (name "Net-(U$4-P1)") (class "Default")
      (node (ref "D4") (pin "A") (pinfunction "A_A") (pintype "passive"))
      (node (ref "U$4") (pin "MX2") (pinfunction "P1_MX2") (pintype "bidirectional"))
    )
    (net (code "31") (name "Net-(U$5-P1)") (class "Default")
      (node (ref "D5") (pin "A") (pinfunction "A_A") (pintype "passive"))
      (node (ref "U$5") (pin "MX2") (pinfunction "P1_MX2") (pintype "bidirectional"))
    )
    (net (code "32") (name "Net-(U$6-P1)") (class "Default")
      (node (ref "D6") (pin "A") (pinfunction "A_A") (pintype "passive"))
      (node (ref "U$6") (pin "MX2") (pinfunction "P1_MX2") (pintype "bidirectional"))
    )
    (net (code "33") (name "Net-(U$7-P1)") (class "Default")
      (node (ref "D7") (pin "A") (pinfunction "A_A") (pintype "passive"))
      (node (ref "U$7") (pin "MX2") (pinfunction "P1_MX2") (pintype "bidirectional"))
    )
    (net (code "34") (name "Net-(U$8-P1)") (class "Default")
      (node (ref "D8") (pin "A") (pinfunction "A_A") (pintype "passive"))
      (node (ref "U$8") (pin "MX2") (pinfunction "P1_MX2") (pintype "bidirectional"))
    )
    (net (code "35") (name "Net-(U$9-P1)") (class "Default")
      (node (ref "D9") (pin "A") (pinfunction "A_A") (pintype "passive"))
      (node (ref "U$9") (pin "MX2") (pinfunction "P1_MX2") (pintype "bidirectional"))
    )
    (net (code "36") (name "Net-(U$10-P1)") (class "Default")
      (node (ref "D10") (pin "A") (pinfunction "A_A") (pintype "passive"))
      (node (ref "U$10") (pin "MX2") (pinfunction "P1_MX2") (pintype "bidirectional"))
    )
    (net (code "37") (name "Net-(U$11-P1)") (class "Default")
      (node (ref "D11") (pin "A") (pinfunction "A_A") (pintype "passive"))
      (node (ref "U$11") (pin "MX2") (pinfunction "P1_MX2") (pintype "bidirectional"))
    )
    (net (code "38") (name "Net-(U$12-P1)") (class "Default")
      (node (ref "D12") (pin "A") (pinfunction "A_A") (pintype "passive"))
      (node (ref "U$12") (pin "MX2") (pinfunction "P1_MX2") (pintype "bidirectional"))
    )
    (net (code "39") (name "Net-(U$13-P1)") (class "Default")
      (node (ref "D13") (pin "A") (pinfunction "A_A") (pintype "passive"))
      (node (ref "U$13") (pin "MX2") (pinfunction "P1_MX2") (pintype "bidirectional"))
    )
    (net (code "40") (name "Net-(U$14-P1)") (class "Default")
      (node (ref "D14") (pin "A") (pinfunction "A_A") (pintype "passive"))
      (node (ref "U$14") (pin "MX2") (pinfunction "P1_MX2") (pintype "bidirectional"))
    )
    (net (code "41") (name "Net-(U$15-P1)") (class "Default")
      (node (ref "D15") (pin "A") (pinfunction "A_A") (pintype "passive"))
      (node (ref "U$15") (pin "MX2") (pinfunction "P1_MX2") (pintype "bidirectional"))
    )
    (net (code "42") (name "Net-(U$16-P1)") (class "Default")
      (node (ref "D16") (pin "A") (pinfunction "A_A") (pintype "passive"))
      (node (ref "U$16") (pin "MX2") (pinfunction "P1_MX2") (pintype "bidirectional"))
    )
    (net (code "43") (name "Net-(U$17-P1)") (class "Default")
      (node (ref "D17") (pin "A") (pinfunction "A_A") (pintype "passive"))
      (node (ref "U$17") (pin "MX2") (pinfunction "P1_MX2") (pintype "bidirectional"))
    )
    (net (code "44") (name "Net-(U$18-P1)") (class "Default")
      (node (ref "D18") (pin "A") (pinfunction "A_A") (pintype "passive"))
      (node (ref "U$18") (pin "MX2") (pinfunction "P1_MX2") (pintype "bidirectional"))
    )
    (net (code "45") (name "Net-(U$19-P1)") (class "Default")
      (node (ref "D19") (pin "A") (pinfunction "A_A") (pintype "passive"))
      (node (ref "U$19") (pin "MX2") (pinfunction "P1_MX2") (pintype "bidirectional"))
    )
    (net (code "46") (name "Net-(U$20-P1)") (class "Default")
      (node (ref "D20") (pin "A") (pinfunction "A_A") (pintype "passive"))
      (node (ref "U$20") (pin "MX2") (pinfunction "P1_MX2") (pintype "bidirectional"))
    )
    (net (code "47") (name "Net-(U$21-P1)") (class "Default")
      (node (ref "D21") (pin "A") (pinfunction "A_A") (pintype "passive"))
      (node (ref "U$21") (pin "MX2") (pinfunction "P1_MX2") (pintype "bidirectional"))
    )
    (net (code "48") (name "Net-(U$22-P1)") (class "Default")
      (node (ref "D22") (pin "A") (pinfunction "A_A") (pintype "passive"))
      (node (ref "U$22") (pin "MX2") (pinfunction "P1_MX2") (pintype "bidirectional"))
    )
    (net (code "49") (name "Net-(U$23-P1)") (class "Default")
      (node (ref "D23") (pin "A") (pinfunction "A_A") (pintype "passive"))
      (node (ref "U$23") (pin "MX2") (pinfunction "P1_MX2") (pintype "bidirectional"))
    )
    (net (code "50") (name "Net-(U$24-P1)") (class "Default")
      (node (ref "D24") (pin "A") (pinfunction "A_A") (pintype "passive"))
      (node (ref "U$24") (pin "MX2") (pinfunction "P1_MX2") (pintype "bidirectional"))
    )
    (net (code "51") (name "Net-(U$25-P1)") (class "Default")
      (node (ref "D25") (pin "A") (pinfunction "A_A") (pintype "passive"))
      (node (ref "U$25") (pin "MX2") (pinfunction "P1_MX2") (pintype "bidirectional"))
    )
    (net (code "52") (name "Net-(U$26-P1)") (class "Default")
      (node (ref "D26") (pin "A") (pinfunction "A_A") (pintype "passive"))
      (node (ref "U$26") (pin "MX2") (pinfunction "P1_MX2") (pintype "bidirectional"))
    )
    (net (code "53") (name "Net-(U$27-P1)") (class "Default")
      (node (ref "D27") (pin "A") (pinfunction "A_A") (pintype "passive"))
      (node (ref "U$27") (pin "MX2") (pinfunction "P1_MX2") (pintype "bidirectional"))
    )
    (net (code "54") (name "Net-(U$28-P1)") (class "Default")
      (node (ref "D28") (pin "A") (pinfunction "A_A") (pintype "passive"))
      (node (ref "U$28") (pin "MX2") (pinfunction "P1_MX2") (pintype "bidirectional"))
    )
    (net (code "55") (name "Net-(U$29-P1)") (class "Default")
      (node (ref "D29") (pin "A") (pinfunction "A_A") (pintype "passive"))
      (node (ref "U$29") (pin "MX2") (pinfunction "P1_MX2") (pintype "bidirectional"))
    )
    (net (code "56") (name "Net-(U$30-P1)") (class "Default")
      (node (ref "D30") (pin "A") (pinfunction "A_A") (pintype "passive"))
      (node (ref "U$30") (pin "MX2") (pinfunction "P1_MX2") (pintype "bidirectional"))
    )
    (net (code "57") (name "Net-(U$31-P1)") (class "Default")
      (node (ref "D31") (pin "A") (pinfunction "A_A") (pintype "passive"))
      (node (ref "U$31") (pin "MX2") (pinfunction "P1_MX2") (pintype "bidirectional"))
    )
    (net (code "58") (name "Net-(U$32-P1)") (class "Default")
      (node (ref "D32") (pin "A") (pinfunction "A_A") (pintype "passive"))
      (node (ref "U$32") (pin "MX2") (pinfunction "P1_MX2") (pintype "bidirectional"))
    )
    (net (code "59") (name "Net-(U$33-P1)") (class "Default")
      (node (ref "D33") (pin "A") (pinfunction "A_A") (pintype "passive"))
      (node (ref "U$33") (pin "MX2") (pinfunction "P1_MX2") (pintype "bidirectional"))
    )
    (net (code "60") (name "Net-(U$34-P1)") (class "Default")
      (node (ref "D34") (pin "A") (pinfunction "A_A") (pintype "passive"))
      (node (ref "U$34") (pin "MX2") (pinfunction "P1_MX2") (pintype "bidirectional"))
    )
    (net (code "61") (name "Net-(U$35-P1)") (class "Default")
      (node (ref "D35") (pin "A") (pinfunction "A_A") (pintype "passive"))
      (node (ref "U$35") (pin "MX2") (pinfunction "P1_MX2") (pintype "bidirectional"))
    )
    (net (code "62") (name "Net-(U$36-P1)") (class "Default")
      (node (ref "D36") (pin "A") (pinfunction "A_A") (pintype "passive"))
      (node (ref "U$36") (pin "MX2") (pinfunction "P1_MX2") (pintype "bidirectional"))
    )
    (net (code "63") (name "Net-(U$37-P1)") (class "Default")
      (node (ref "D37") (pin "A") (pinfunction "A_A") (pintype "passive"))
      (node (ref "U$37") (pin "MX2") (pinfunction "P1_MX2") (pintype "bidirectional"))
    )
    (net (code "64") (name "Net-(U$38-P1)") (class "Default")
      (node (ref "D38") (pin "A") (pinfunction "A_A") (pintype "passive"))
      (node (ref "U$38") (pin "MX2") (pinfunction "P1_MX2") (pintype "bidirectional"))
    )
    (net (code "65") (name "Net-(U$39-P1)") (class "Default")
      (node (ref "D39") (pin "A") (pinfunction "A_A") (pintype "passive"))
      (node (ref "U$39") (pin "MX2") (pinfunction "P1_MX2") (pintype "bidirectional"))
    )
    (net (code "66") (name "Net-(U$40-P1)") (class "Default")
      (node (ref "D40") (pin "A") (pinfunction "A_A") (pintype "passive"))
      (node (ref "U$40") (pin "MX2") (pinfunction "P1_MX2") (pintype "bidirectional"))
    )
    (net (code "67") (name "Net-(U$41-P1)") (class "Default")
      (node (ref "D41") (pin "A") (pinfunction "A_A") (pintype "passive"))
      (node (ref "U$41") (pin "MX2") (pinfunction "P1_MX2") (pintype "bidirectional"))
    )
    (net (code "68") (name "Net-(U$42-P1)") (class "Default")
      (node (ref "D42") (pin "A") (pinfunction "A_A") (pintype "passive"))
      (node (ref "U$42") (pin "MX2") (pinfunction "P1_MX2") (pintype "bidirectional"))
    )
    (net (code "69") (name "Net-(U$43-P1)") (class "Default")
      (node (ref "D43") (pin "A") (pinfunction "A_A") (pintype "passive"))
      (node (ref "U$43") (pin "MX2") (pinfunction "P1_MX2") (pintype "bidirectional"))
    )
    (net (code "70") (name "Net-(U$44-P1)") (class "Default")
      (node (ref "D44") (pin "A") (pinfunction "A_A") (pintype "passive"))
      (node (ref "U$44") (pin "MX2") (pinfunction "P1_MX2") (pintype "bidirectional"))
    )
    (net (code "71") (name "Net-(U$45-P1)") (class "Default")
      (node (ref "D45") (pin "A") (pinfunction "A_A") (pintype "passive"))
      (node (ref "U$45") (pin "MX2") (pinfunction "P1_MX2") (pintype "bidirectional"))
    )
    (net (code "72") (name "Net-(U$46-P1)") (class "Default")
      (node (ref "D46") (pin "A") (pinfunction "A_A") (pintype "passive"))
      (node (ref "U$46") (pin "MX2") (pinfunction "P1_MX2") (pintype "bidirectional"))
    )
    (net (code "73") (name "Net-(U$47-P1)") (class "Default")
      (node (ref "D47") (pin "A") (pinfunction "A_A") (pintype "passive"))
      (node (ref "U$47") (pin "MX2") (pinfunction "P1_MX2") (pintype "bidirectional"))
    )
    (net (code "74") (name "Net-(U$48-P1)") (class "Default")
      (node (ref "D48") (pin "A") (pinfunction "A_A") (pintype "passive"))
      (node (ref "U$48") (pin "MX2") (pinfunction "P1_MX2") (pintype "bidirectional"))
    )
    (net (code "75") (name "Net-(U$49-P1)") (class "Default")
      (node (ref "D49") (pin "A") (pinfunction "A_A") (pintype "passive"))
      (node (ref "U$49") (pin "MX2") (pinfunction "P1_MX2") (pintype "bidirectional"))
    )
    (net (code "76") (name "Net-(U$50-P1)") (class "Default")
      (node (ref "D50") (pin "A") (pinfunction "A_A") (pintype "passive"))
      (node (ref "U$50") (pin "MX2") (pinfunction "P1_MX2") (pintype "bidirectional"))
    )
    (net (code "77") (name "Net-(U$51-P1)") (class "Default")
      (node (ref "D51") (pin "A") (pinfunction "A_A") (pintype "passive"))
      (node (ref "U$51") (pin "MX2") (pinfunction "P1_MX2") (pintype "bidirectional"))
    )
    (net (code "78") (name "Net-(U$52-P1)") (class "Default")
      (node (ref "D52") (pin "A") (pinfunction "A_A") (pintype "passive"))
      (node (ref "U$52") (pin "MX2") (pinfunction "P1_MX2") (pintype "bidirectional"))
    )
    (net (code "79") (name "Net-(U$53-P1)") (class "Default")
      (node (ref "D53") (pin "A") (pinfunction "A_A") (pintype "passive"))
      (node (ref "U$53") (pin "MX2") (pinfunction "P1_MX2") (pintype "bidirectional"))
    )
    (net (code "80") (name "Net-(U$54-P1)") (class "Default")
      (node (ref "D54") (pin "A") (pinfunction "A_A") (pintype "passive"))
      (node (ref "U$54") (pin "MX2") (pinfunction "P1_MX2") (pintype "bidirectional"))
    )
    (net (code "81") (name "Net-(U$55-P1)") (class "Default")
      (node (ref "D55") (pin "A") (pinfunction "A_A") (pintype "passive"))
      (node (ref "U$55") (pin "MX2") (pinfunction "P1_MX2") (pintype "bidirectional"))
    )
    (net (code "82") (name "Net-(U$56-P1)") (class "Default")
      (node (ref "D56") (pin "A") (pinfunction "A_A") (pintype "passive"))
      (node (ref "U$56") (pin "MX2") (pinfunction "P1_MX2") (pintype "bidirectional"))
    )
    (net (code "83") (name "Net-(U$57-P1)") (class "Default")
      (node (ref "D57") (pin "A") (pinfunction "A_A") (pintype "passive"))
      (node (ref "U$57") (pin "MX2") (pinfunction "P1_MX2") (pintype "bidirectional"))
    )
    (net (code "84") (name "Net-(U$58-P1)") (class "Default")
      (node (ref "D58") (pin "A") (pinfunction "A_A") (pintype "passive"))
      (node (ref "U$58") (pin "MX2") (pinfunction "P1_MX2") (pintype "bidirectional"))
    )
    (net (code "85") (name "Net-(U$59-P1)") (class "Default")
      (node (ref "D59") (pin "A") (pinfunction "A_A") (pintype "passive"))
      (node (ref "U$59") (pin "MX2") (pinfunction "P1_MX2") (pintype "bidirectional"))
    )
    (net (code "86") (name "Net-(U$60-P1)") (class "Default")
      (node (ref "D60") (pin "A") (pinfunction "A_A") (pintype "passive"))
      (node (ref "U$60") (pin "MX2") (pinfunction "P1_MX2") (pintype "bidirectional"))
    )
    (net (code "87") (name "Net-(U$61-P1)") (class "Default")
      (node (ref "D61") (pin "A") (pinfunction "A_A") (pintype "passive"))
      (node (ref "U$61") (pin "MX2") (pinfunction "P1_MX2") (pintype "bidirectional"))
    )
    (net (code "88") (name "Net-(U$62-P1)") (class "Default")
      (node (ref "D62") (pin "A") (pinfunction "A_A") (pintype "passive"))
      (node (ref "U$62") (pin "MX2") (pinfunction "P1_MX2") (pintype "bidirectional"))
    )
    (net (code "89") (name "Net-(U$63-P1)") (class "Default")
      (node (ref "D63") (pin "A") (pinfunction "A_A") (pintype "passive"))
      (node (ref "U$63") (pin "MX2") (pinfunction "P1_MX2") (pintype "bidirectional"))
    )
    (net (code "90") (name "Net-(U$65-PE2(~{HWB}))") (class "Default")
      (node (ref "R2") (pin "2") (pinfunction "2_2") (pintype "passive"))
      (node (ref "U$65") (pin "33") (pinfunction "PE2(~{HWB})_33") (pintype "bidirectional"))
    )
    (net (code "91") (name "Net-(U$65-UCAP)") (class "Default")
      (node (ref "C8") (pin "1") (pinfunction "1_1") (pintype "passive"))
      (node (ref "U$65") (pin "6") (pinfunction "UCAP_6") (pintype "bidirectional"))
    )
    (net (code "92") (name "ROW1") (class "Default")
      (node (ref "D1") (pin "C") (pinfunction "C_C") (pintype "passive"))
      (node (ref "D10") (pin "C") (pinfunction "C_C") (pintype "passive"))
      (node (ref "D11") (pin "C") (pinfunction "C_C") (pintype "passive"))
      (node (ref "D12") (pin "C") (pinfunction "C_C") (pintype "passive"))
      (node (ref "D13") (pin "C") (pinfunction "C_C") (pintype "passive"))
      (node (ref "D14") (pin "C") (pinfunction "C_C") (pintype "passive"))
      (node (ref "D2") (pin "C") (pinfunction "C_C") (pintype "passive"))
      (node (ref "D3") (pin "C") (pinfunction "C_C") (pintype "passive"))
      (node (ref "D4") (pin "C") (pinfunction "C_C") (pintype "passive"))
      (node (ref "D5") (pin "C") (pinfunction "C_C") (pintype "passive"))
      (node (ref "D6") (pin "C") (pinfunction "C_C") (pintype "passive"))
      (node (ref "D7") (pin "C") (pinfunction "C_C") (pintype "passive"))
      (node (ref "D8") (pin "C") (pinfunction "C_C") (pintype "passive"))
      (node (ref "D9") (pin "C") (pinfunction "C_C") (pintype "passive"))
      (node (ref "U$65") (pin "40") (pinfunction "PF1(ADC1)_40") (pintype "bidirectional"))
    )
    (net (code "93") (name "ROW2") (class "Default")
      (node (ref "D15") (pin "C") (pinfunction "C_C") (pintype "passive"))
      (node (ref "D16") (pin "C") (pinfunction "C_C") (pintype "passive"))
      (node (ref "D17") (pin "C") (pinfunction "C_C") (pintype "passive"))
      (node (ref "D18") (pin "C") (pinfunction "C_C") (pintype "passive"))
      (node (ref "D19") (pin "C") (pinfunction "C_C") (pintype "passive"))
      (node (ref "D20") (pin "C") (pinfunction "C_C") (pintype "passive"))
      (node (ref "D21") (pin "C") (pinfunction "C_C") (pintype "passive"))
      (node (ref "D22") (pin "C") (pinfunction "C_C") (pintype "passive"))
      (node (ref "D23") (pin "C") (pinfunction "C_C") (pintype "passive"))
      (node (ref "D24") (pin "C") (pinfunction "C_C") (pintype "passive"))
      (node (ref "D25") (pin "C") (pinfunction "C_C") (pintype "passive"))
      (node (ref "D26") (pin "C") (pinfunction "C_C") (pintype "passive"))
      (node (ref "D27") (pin "C") (pinfunction "C_C") (pintype "passive"))
      (node (ref "D28") (pin "C") (pinfunction "C_C") (pintype "passive"))
      (node (ref "U$65") (pin "41") (pinfunction "PF0(ADC0)_41") (pintype "bidirectional"))
    )
    (net (code "94") (name "ROW3") (class "Default")
      (node (ref "D29") (pin "C") (pinfunction "C_C") (pintype "passive"))
      (node (ref "D30") (pin "C") (pinfunction "C_C") (pintype "passive"))
      (node (ref "D31") (pin "C") (pinfunction "C_C") (pintype "passive"))
      (node (ref "D32") (pin "C") (pinfunction "C_C") (pintype "passive"))
      (node (ref "D33") (pin "C") (pinfunction "C_C") (pintype "passive"))
      (node (ref "D34") (pin "C") (pinfunction "C_C") (pintype "passive"))
      (node (ref "D35") (pin "C") (pinfunction "C_C") (pintype "passive"))
      (node (ref "D36") (pin "C") (pinfunction "C_C") (pintype "passive"))
      (node (ref "D37") (pin "C") (pinfunction "C_C") (pintype "passive"))
      (node (ref "D38") (pin "C") (pinfunction "C_C") (pintype "passive"))
      (node (ref "D39") (pin "C") (pinfunction "C_C") (pintype "passive"))
      (node (ref "D40") (pin "C") (pinfunction "C_C") (pintype "passive"))
      (node (ref "D41") (pin "C") (pinfunction "C_C") (pintype "passive"))
      (node (ref "U$65") (pin "1") (pinfunction "PE6(INT.6/AIN0)_1") (pintype "bidirectional"))
    )
    (net (code "95") (name "ROW4") (class "Default")
      (node (ref "D42") (pin "C") (pinfunction "C_C") (pintype "passive"))
      (node (ref "D43") (pin "C") (pinfunction "C_C") (pintype "passive"))
      (node (ref "D44") (pin "C") (pinfunction "C_C") (pintype "passive"))
      (node (ref "D45") (pin "C") (pinfunction "C_C") (pintype "passive"))
      (node (ref "D46") (pin "C") (pinfunction "C_C") (pintype "passive"))
      (node (ref "D47") (pin "C") (pinfunction "C_C") (pintype "passive"))
      (node (ref "D48") (pin "C") (pinfunction "C_C") (pintype "passive"))
      (node (ref "D49") (pin "C") (pinfunction "C_C") (pintype "passive"))
      (node (ref "D50") (pin "C") (pinfunction "C_C") (pintype "passive"))
      (node (ref "D51") (pin "C") (pinfunction "C_C") (pintype "passive"))
      (node (ref "D52") (pin "C") (pinfunction "C_C") (pintype "passive"))
      (node (ref "D53") (pin "C") (pinfunction "C_C") (pintype "passive"))
      (node (ref "D54") (pin "C") (pinfunction "C_C") (pintype "passive"))
      (node (ref "U$65") (pin "32") (pinfunction "PC7(ICP3/CLK0/OC4A)_32") (pintype "bidirectional"))
    )
    (net (code "96") (name "ROW5") (class "Default")
      (node (ref "D55") (pin "C") (pinfunction "C_C") (pintype "passive"))
      (node (ref "D56") (pin "C") (pinfunction "C_C") (pintype "passive"))
      (node (ref "D57") (pin "C") (pinfunction "C_C") (pintype "passive"))
      (node (ref "D58") (pin "C") (pinfunction "C_C") (pintype "passive"))
      (node (ref "D59") (pin "C") (pinfunction "C_C") (pintype "passive"))
      (node (ref "D60") (pin "C") (pinfunction "C_C") (pintype "passive"))
      (node (ref "D61") (pin "C") (pinfunction "C_C") (pintype "passive"))
      (node (ref "D62") (pin "C") (pinfunction "C_C") (pintype "passive"))
      (node (ref "D63") (pin "C") (pinfunction "C_C") (pintype "passive"))
      (node (ref "U$65") (pin "12") (pinfunction "PB7(PCINT7/OC0A/OC1C/~{RTS})_12") (pintype "bidirectional"))
    )
    (net (code "97") (name "unconnected-(J1-ID-Pad4)") (class "Default")
      (node (ref "J1") (pin "4") (pinfunction "ID_4") (pintype "bidirectional"))
    )
    (net (code "98") (name "unconnected-(SW1-Pad1)") (class "Default")
      (node (ref "SW1") (pin "1") (pinfunction "1_1") (pintype "passive"))
    )
    (net (code "99") (name "unconnected-(SW1-Pad4)") (class "Default")
      (node (ref "SW1") (pin "4") (pinfunction "4_4") (pintype "passive"))
    )
    (net (code "100") (name "unconnected-(U$65-AREF-Pad42)") (class "Default")
      (node (ref "U$65") (pin "42") (pinfunction "AREF_42") (pintype "bidirectional"))
    )
    (net (code "101") (name "unconnected-(U$65-PB0(SS{slash}PCINT0)-Pad8)") (class "Default")
      (node (ref "U$65") (pin "8") (pinfunction "PB0(SS/PCINT0)_8") (pintype "bidirectional"))
    )
    (net (code "102") (name "unconnected-(U$65-PD0(OC0B{slash}SCL{slash}INT0)-Pad18)") (class "Default")
      (node (ref "U$65") (pin "18") (pinfunction "PD0(OC0B/SCL/INT0)_18") (pintype "bidirectional"))
    )
    (net (code "103") (name "unconnected-(U$65-PD5(XCLK1{slash}~{CTS})-Pad22)") (class "Default")
      (node (ref "U$65") (pin "22") (pinfunction "PD5(XCLK1/~{CTS})_22") (pintype "bidirectional"))
    )
  )
)
